# StepperBoard.net
KiCad netlist of a schematic drawn in EAGLE
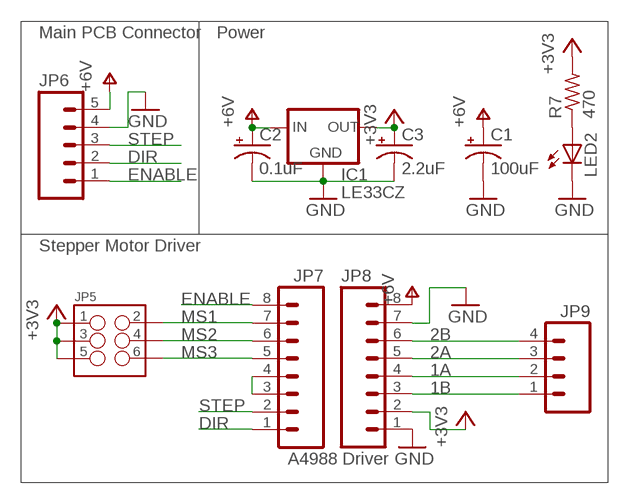
[diagram p0: schematic, sheet 1]

(export (version "E")
  (design (tool "Eeschema 10.0.6"))
  (components
    (comp (ref "C1")
      (value "100uF")
      (footprint "eagle-import:E3,5-8")
      (libsource (lib "eagle-import") (part "CPOL-USE3.5-8"))
    )
    (comp (ref "C2")
      (value "0.1uF")
      (footprint "eagle-import:E3,5-8")
      (libsource (lib "eagle-import") (part "CPOL-USE3.5-8"))
    )
    (comp (ref "C3")
      (value "2.2uF")
      (footprint "eagle-import:E3,5-8")
      (libsource (lib "eagle-import") (part "CPOL-USE3.5-8"))
    )
    (comp (ref "IC1")
      (value "LE33CZ")
      (footprint "eagle-import:TO-92")
      (libsource (lib "eagle-import") (part "V_REG_78XXTO-92"))
    )
    (comp (ref "JP5")
      (value "M03X2")
      (footprint "eagle-import:2X3-SHROUDED")
      (libsource (lib "eagle-import") (part "M03X2"))
    )
    (comp (ref "JP6")
      (value "M05PTH")
      (footprint "eagle-import:1X05")
      (libsource (lib "eagle-import") (part "M05PTH"))
    )
    (comp (ref "JP7")
      (value "M081X08")
      (footprint "eagle-import:1X08")
      (libsource (lib "eagle-import") (part "M081X08"))
    )
    (comp (ref "JP8")
      (value "M081X08")
      (footprint "eagle-import:1X08")
      (libsource (lib "eagle-import") (part "M081X08"))
    )
    (comp (ref "JP9")
      (value "M04PTH")
      (footprint "eagle-import:1X04")
      (libsource (lib "eagle-import") (part "M04PTH"))
    )
    (comp (ref "LED2")
      (value "LEDCHIP-LED0805")
      (footprint "eagle-import:CHIP-LED0805")
      (libsource (lib "eagle-import") (part "LEDCHIP-LED0805"))
    )
    (comp (ref "R7")
      (value "470")
      (footprint "eagle-import:R0805")
      (libsource (lib "eagle-import") (part "R-US_R0805"))
    )
  )
  (nets
    (net (code "1") (name "+3V3") (class "Default")
      (node (ref "C3") (pin "+") (pinfunction "+_+") (pintype "passive"))
      (node (ref "IC1") (pin "3") (pinfunction "OUT_3") (pintype "output"))
      (node (ref "JP5") (pin "1") (pinfunction "1_1") (pintype "bidirectional"))
      (node (ref "JP5") (pin "3") (pinfunction "3_3") (pintype "bidirectional"))
      (node (ref "JP5") (pin "5") (pinfunction "5_5") (pintype "bidirectional"))
      (node (ref "JP8") (pin "2") (pinfunction "2_2") (pintype "passive"))
      (node (ref "R7") (pin "2") (pinfunction "2_2") (pintype "passive"))
    )
    (net (code "2") (name "+6V") (class "Default")
      (node (ref "C1") (pin "+") (pinfunction "+_+") (pintype "passive"))
      (node (ref "C2") (pin "+") (pinfunction "+_+") (pintype "passive"))
      (node (ref "IC1") (pin "2") (pinfunction "IN_2") (pintype "input"))
      (node (ref "JP6") (pin "5") (pinfunction "5_5") (pintype "passive"))
      (node (ref "JP8") (pin "8") (pinfunction "8_8") (pintype "passive"))
    )
    (net (code "3") (name "/1A") (class "Default")
      (node (ref "JP8") (pin "4") (pinfunction "4_4") (pintype "passive"))
      (node (ref "JP9") (pin "2") (pinfunction "2_2") (pintype "passive"))
    )
    (net (code "4") (name "/1B") (class "Default")
      (node (ref "JP8") (pin "3") (pinfunction "3_3") (pintype "passive"))
      (node (ref "JP9") (pin "1") (pinfunction "1_1") (pintype "passive"))
    )
    (net (code "5") (name "/2A") (class "Default")
      (node (ref "JP8") (pin "5") (pinfunction "5_5") (pintype "passive"))
      (node (ref "JP9") (pin "3") (pinfunction "3_3") (pintype "passive"))
    )
    (net (code "6") (name "/2B") (class "Default")
      (node (ref "JP8") (pin "6") (pinfunction "6_6") (pintype "passive"))
      (node (ref "JP9") (pin "4") (pinfunction "4_4") (pintype "passive"))
    )
    (net (code "7") (name "/DIR") (class "Default")
      (node (ref "JP6") (pin "2") (pinfunction "2_2") (pintype "passive"))
      (node (ref "JP7") (pin "1") (pinfunction "1_1") (pintype "passive"))
    )
    (net (code "8") (name "/ENABLE") (class "Default")
      (node (ref "JP6") (pin "1") (pinfunction "1_1") (pintype "passive"))
      (node (ref "JP7") (pin "8") (pinfunction "8_8") (pintype "passive"))
    )
    (net (code "9") (name "/MS1") (class "Default")
      (node (ref "JP5") (pin "2") (pinfunction "2_2") (pintype "bidirectional"))
      (node (ref "JP7") (pin "7") (pinfunction "7_7") (pintype "passive"))
    )
    (net (code "10") (name "/MS2") (class "Default")
      (node (ref "JP5") (pin "4") (pinfunction "4_4") (pintype "bidirectional"))
      (node (ref "JP7") (pin "6") (pinfunction "6_6") (pintype "passive"))
    )
    (net (code "11") (name "/MS3") (class "Default")
      (node (ref "JP5") (pin "6") (pinfunction "6_6") (pintype "bidirectional"))
      (node (ref "JP7") (pin "5") (pinfunction "5_5") (pintype "passive"))
    )
    (net (code "12") (name "/STEP") (class "Default")
      (node (ref "JP6") (pin "3") (pinfunction "3_3") (pintype "passive"))
      (node (ref "JP7") (pin "2") (pinfunction "2_2") (pintype "passive"))
    )
    (net (code "13") (name "GND") (class "Default")
      (node (ref "C1") (pin "-") (pinfunction "-_-") (pintype "passive"))
      (node (ref "C2") (pin "-") (pinfunction "-_-") (pintype "passive"))
      (node (ref "C3") (pin "-") (pinfunction "-_-") (pintype "passive"))
      (node (ref "IC1") (pin "1") (pinfunction "GND_1") (pintype "input"))
      (node (ref "JP6") (pin "4") (pinfunction "4_4") (pintype "passive"))
      (node (ref "JP8") (pin "1") (pinfunction "1_1") (pintype "passive"))
      (node (ref "JP8") (pin "7") (pinfunction "7_7") (pintype "passive"))
      (node (ref "LED2") (pin "C") (pinfunction "C_C") (pintype "passive"))
    )
    (net (code "14") (name "Net-(JP7-Pad3)") (class "Default")
      (node (ref "JP7") (pin "3") (pinfunction "3_3") (pintype "passive"))
      (node (ref "JP7") (pin "4") (pinfunction "4_4") (pintype "passive"))
    )
    (net (code "15") (name "Net-(LED2-PadA)") (class "Default")
      (node (ref "LED2") (pin "A") (pinfunction "A_A") (pintype "passive"))
      (node (ref "R7") (pin "1") (pinfunction "1_1") (pintype "passive"))
    )
  )
)
